# Incoming_connectors2.net
KiCad netlist of a schematic drawn in Altium Designer
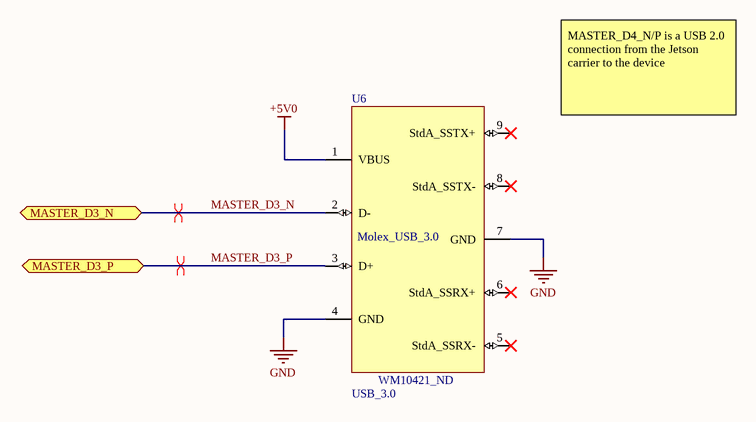
[diagram p0: Incoming_connectors2.SchDoc]

(export (version "E")
  (design (tool "Eeschema 10.0.6"))
  (components
    (comp (ref "U6")
      (value "USB_3.0")
      (footprint "RSX_Connectors:Molex_USB_3.0_WM10421_ND")
      (description "USB 3.0 Type A Receptacle Connector 9 Position Through Hole")
      (fields (field (name "MANUFACTURER") "Molex"))
      (libsource (lib "RSX_Connectors") (part "Molex_USB_3.0_WM10421_ND"))
    )
  )
  (nets
    (net (code "1") (name "+5V0") (class "Default")
      (node (ref "U6") (pin "1") (pinfunction "VBUS_1") (pintype "passive"))
    )
    (net (code "3") (name "/MASTER_D3_N") (class "Default")
      (node (ref "U6") (pin "2") (pinfunction "D-_2") (pintype "bidirectional"))
    )
    (net (code "4") (name "/MASTER_D3_P") (class "Default")
      (node (ref "U6") (pin "3") (pinfunction "D+_3") (pintype "bidirectional"))
    )
    (net (code "5") (name "GND") (class "Default")
      (node (ref "U6") (pin "4") (pinfunction "GND_4") (pintype "passive"))
      (node (ref "U6") (pin "7") (pinfunction "GND_7") (pintype "passive"))
    )
    (net (code "6") (name "unconnected-(U6-StdA_SSRX+-Pad6)") (class "Default")
      (node (ref "U6") (pin "6") (pinfunction "StdA_SSRX+_6") (pintype "bidirectional+no_connect"))
    )
    (net (code "7") (name "unconnected-(U6-StdA_SSRX--Pad5)") (class "Default")
      (node (ref "U6") (pin "5") (pinfunction "StdA_SSRX-_5") (pintype "bidirectional+no_connect"))
    )
    (net (code "8") (name "unconnected-(U6-StdA_SSTX+-Pad9)") (class "Default")
      (node (ref "U6") (pin "9") (pinfunction "StdA_SSTX+_9") (pintype "bidirectional+no_connect"))
    )
    (net (code "9") (name "unconnected-(U6-StdA_SSTX--Pad8)") (class "Default")
      (node (ref "U6") (pin "8") (pinfunction "StdA_SSTX-_8") (pintype "bidirectional+no_connect"))
    )
  )
)
